# rs232_conn.net
KiCad netlist of a schematic drawn in Altium Designer
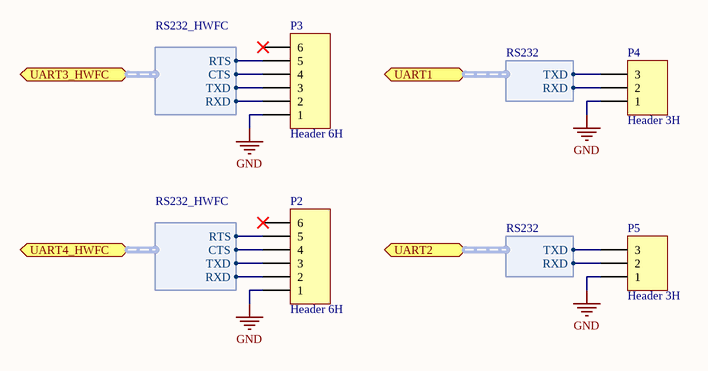
[diagram p0: rs232_conn.SchDoc]

(export (version "E")
  (design (tool "Eeschema 10.0.6"))
  (components
    (comp (ref "P2")
      (value "Header 6H")
      (footprint "S06B-PASK-2")
      (description "Header, 6-Pin, Right Angle")
      (fields (field (name "PUBLISHER") "Altium Limited"))
      (libsource (lib "Miscellaneous Connectors") (part "Header 6H"))
    )
    (comp (ref "P3")
      (value "Header 6H")
      (footprint "S06B-PASK-2")
      (description "Header, 6-Pin, Right Angle")
      (fields (field (name "PUBLISHER") "Altium Limited"))
      (libsource (lib "Miscellaneous Connectors") (part "Header 6H"))
    )
    (comp (ref "P4")
      (value "Header 3H")
      (footprint "S03B-PASK-2")
      (description "Header, 3-Pin, Right Angle")
      (fields (field (name "PUBLISHER") "Altium Limited"))
      (libsource (lib "Miscellaneous Connectors") (part "Header 3H"))
    )
    (comp (ref "P5")
      (value "Header 3H")
      (footprint "S03B-PASK-2")
      (description "Header, 3-Pin, Right Angle")
      (fields (field (name "PUBLISHER") "Altium Limited"))
      (libsource (lib "Miscellaneous Connectors") (part "Header 3H"))
    )
  )
  (nets
    (net (code "5") (name "GND") (class "Default")
      (node (ref "P2") (pin "1") (pinfunction "1_1") (pintype "passive"))
      (node (ref "P3") (pin "1") (pinfunction "1_1") (pintype "passive"))
      (node (ref "P4") (pin "1") (pinfunction "1_1") (pintype "passive"))
      (node (ref "P5") (pin "1") (pinfunction "1_1") (pintype "passive"))
    )
    (net (code "6") (name "unconnected-(P2-Pad2)") (class "Default")
      (node (ref "P2") (pin "2") (pinfunction "2_2") (pintype "passive"))
    )
    (net (code "7") (name "unconnected-(P2-Pad3)") (class "Default")
      (node (ref "P2") (pin "3") (pinfunction "3_3") (pintype "passive"))
    )
    (net (code "8") (name "unconnected-(P2-Pad4)") (class "Default")
      (node (ref "P2") (pin "4") (pinfunction "4_4") (pintype "passive"))
    )
    (net (code "9") (name "unconnected-(P2-Pad5)") (class "Default")
      (node (ref "P2") (pin "5") (pinfunction "5_5") (pintype "passive"))
    )
    (net (code "10") (name "unconnected-(P2-Pad6)") (class "Default")
      (node (ref "P2") (pin "6") (pinfunction "6_6") (pintype "passive+no_connect"))
    )
    (net (code "11") (name "unconnected-(P3-Pad2)") (class "Default")
      (node (ref "P3") (pin "2") (pinfunction "2_2") (pintype "passive"))
    )
    (net (code "12") (name "unconnected-(P3-Pad3)") (class "Default")
      (node (ref "P3") (pin "3") (pinfunction "3_3") (pintype "passive"))
    )
    (net (code "13") (name "unconnected-(P3-Pad4)") (class "Default")
      (node (ref "P3") (pin "4") (pinfunction "4_4") (pintype "passive"))
    )
    (net (code "14") (name "unconnected-(P3-Pad5)") (class "Default")
      (node (ref "P3") (pin "5") (pinfunction "5_5") (pintype "passive"))
    )
    (net (code "15") (name "unconnected-(P3-Pad6)") (class "Default")
      (node (ref "P3") (pin "6") (pinfunction "6_6") (pintype "passive+no_connect"))
    )
    (net (code "16") (name "unconnected-(P4-Pad2)") (class "Default")
      (node (ref "P4") (pin "2") (pinfunction "2_2") (pintype "passive"))
    )
    (net (code "17") (name "unconnected-(P4-Pad3)") (class "Default")
      (node (ref "P4") (pin "3") (pinfunction "3_3") (pintype "passive"))
    )
    (net (code "18") (name "unconnected-(P5-Pad2)") (class "Default")
      (node (ref "P5") (pin "2") (pinfunction "2_2") (pintype "passive"))
    )
    (net (code "19") (name "unconnected-(P5-Pad3)") (class "Default")
      (node (ref "P5") (pin "3") (pinfunction "3_3") (pintype "passive"))
    )
  )
)
